# rs485.net
KiCad netlist of a schematic drawn in Altium Designer
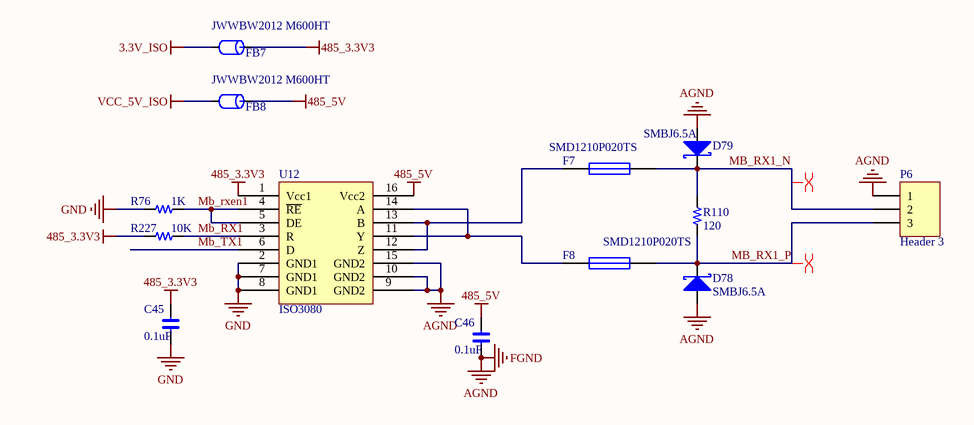
[diagram p0: rs485.SchDoc]

(export (version "E")
  (design (tool "Eeschema 10.0.6"))
  (components
    (comp (ref "C45")
      (value "0.1uF")
      (footprint "0603C")
      (description "C")
      (libsource (lib "Schlib_20110825") (part "C"))
    )
    (comp (ref "C46")
      (value "0.1uF")
      (footprint "0603C")
      (description "C")
      (libsource (lib "Schlib_20110825") (part "C"))
    )
    (comp (ref "D78")
      (value "SMBJ6.5A")
      (footprint "SMB")
      (description "Schottky Diode")
      (libsource (lib "*") (part "DIODE S"))
    )
    (comp (ref "D79")
      (value "SMBJ6.5A")
      (footprint "SMB")
      (description "Schottky Diode")
      (libsource (lib "*") (part "DIODE S"))
    )
    (comp (ref "F7")
      (value "SMD1210P020TS")
      (footprint "1206R")
      (description "Fuse")
      (fields (field (name "PUBLISHER") "Altium Limited"))
      (libsource (lib "Miscellaneous Devices") (part "Fuse 1"))
    )
    (comp (ref "F8")
      (value "SMD1210P020TS")
      (footprint "1206R")
      (description "Fuse")
      (fields (field (name "PUBLISHER") "Altium Limited"))
      (libsource (lib "Miscellaneous Devices") (part "Fuse 1"))
    )
    (comp (ref "FB7")
      (value "JWWBW2012 M600HT")
      (footprint "0805CZ")
      (libsource (lib "Schlib_20110825") (part "FB"))
    )
    (comp (ref "FB8")
      (value "JWWBW2012 M600HT")
      (footprint "0805CZ")
      (libsource (lib "Schlib_20110825") (part "FB"))
    )
    (comp (ref "P6")
      (value "Header 3")
      (footprint "2ETYR-5.08-03P-14-100")
      (description "Header, 3-Pin")
      (fields (field (name "PUBLISHER") "Altium Limited"))
      (libsource (lib "Miscellaneous Connectors") (part "Header 3"))
    )
    (comp (ref "R76") (value "1K") (footprint "0603R") (description "R") (libsource (lib "JRJ_1") (part "R")))
    (comp (ref "R110")
      (value "120")
      (footprint "0603R")
      (description "R")
      (libsource (lib "JRJ_1") (part "R"))
    )
    (comp (ref "R227")
      (value "10K")
      (footprint "0603R")
      (description "R")
      (libsource (lib "JRJ_1") (part "R"))
    )
    (comp (ref "U12") (value "ISO3080") (footprint "SO-16") (libsource (lib "Schlib1") (part "ISO3080")))
  )
  (nets
    (net (code "1") (name "/MB_RX1_N") (class "Default")
      (node (ref "D79") (pin "2") (pinfunction "K_2") (pintype "passive"))
      (node (ref "F7") (pin "2") (pinfunction "2_2") (pintype "passive"))
      (node (ref "P6") (pin "2") (pinfunction "2_2") (pintype "passive"))
      (node (ref "R110") (pin "1") (pintype "passive"))
    )
    (net (code "2") (name "/MB_RX1_P") (class "Default")
      (node (ref "D78") (pin "2") (pinfunction "K_2") (pintype "passive"))
      (node (ref "F8") (pin "2") (pinfunction "2_2") (pintype "passive"))
      (node (ref "P6") (pin "3") (pinfunction "3_3") (pintype "passive"))
      (node (ref "R110") (pin "2") (pintype "passive"))
    )
    (net (code "3") (name "/Mb_RX1") (class "Default")
      (node (ref "R227") (pin "1") (pintype "passive"))
      (node (ref "U12") (pin "3") (pinfunction "R_3") (pintype "passive"))
    )
    (net (code "4") (name "/Mb_TX1") (class "Default")
      (node (ref "U12") (pin "6") (pinfunction "D_6") (pintype "passive"))
    )
    (net (code "5") (name "/Mb_rxen1") (class "Default")
      (node (ref "R76") (pin "1") (pintype "passive"))
      (node (ref "U12") (pin "4") (pinfunction "~{RE}_4") (pintype "passive"))
      (node (ref "U12") (pin "5") (pinfunction "DE_5") (pintype "passive"))
    )
    (net (code "6") (name "3.3V_ISO") (class "Default") (node (ref "FB7") (pin "2") (pintype "passive")))
    (net (code "7") (name "485_3.3V3") (class "Default")
      (node (ref "C45") (pin "2") (pintype "passive"))
      (node (ref "FB7") (pin "1") (pintype "passive"))
      (node (ref "R227") (pin "2") (pintype "passive"))
      (node (ref "U12") (pin "1") (pinfunction "Vcc1_1") (pintype "passive"))
    )
    (net (code "8") (name "485_5V") (class "Default")
      (node (ref "C46") (pin "2") (pintype "passive"))
      (node (ref "FB8") (pin "1") (pintype "passive"))
      (node (ref "U12") (pin "16") (pinfunction "Vcc2_16") (pintype "passive"))
    )
    (net (code "9") (name "AGND") (class "Default")
      (node (ref "C46") (pin "1") (pintype "passive"))
      (node (ref "D78") (pin "1") (pinfunction "A_1") (pintype "passive"))
      (node (ref "D79") (pin "1") (pinfunction "A_1") (pintype "passive"))
      (node (ref "P6") (pin "1") (pinfunction "1_1") (pintype "passive"))
      (node (ref "U12") (pin "10") (pinfunction "GND2_10") (pintype "passive"))
      (node (ref "U12") (pin "15") (pinfunction "GND2_15") (pintype "passive"))
      (node (ref "U12") (pin "9") (pinfunction "GND2_9") (pintype "passive"))
    )
    (net (code "10") (name "GND") (class "Default")
      (node (ref "C45") (pin "1") (pintype "passive"))
      (node (ref "R76") (pin "2") (pintype "passive"))
      (node (ref "U12") (pin "2") (pinfunction "GND1_2") (pintype "passive"))
      (node (ref "U12") (pin "7") (pinfunction "GND1_7") (pintype "passive"))
      (node (ref "U12") (pin "8") (pinfunction "GND1_8") (pintype "passive"))
    )
    (net (code "11") (name "Net-(U12-A)") (class "Default")
      (node (ref "F8") (pin "1") (pinfunction "1_1") (pintype "passive"))
      (node (ref "U12") (pin "11") (pinfunction "Y_11") (pintype "passive"))
      (node (ref "U12") (pin "14") (pinfunction "A_14") (pintype "passive"))
    )
    (net (code "12") (name "Net-(U12-B)") (class "Default")
      (node (ref "F7") (pin "1") (pinfunction "1_1") (pintype "passive"))
      (node (ref "U12") (pin "12") (pinfunction "Z_12") (pintype "passive"))
      (node (ref "U12") (pin "13") (pinfunction "B_13") (pintype "passive"))
    )
    (net (code "13") (name "VCC_5V_ISO") (class "Default") (node (ref "FB8") (pin "2") (pintype "passive")))
  )
)
